# CV_Switch.net
KiCad netlist of a schematic drawn in EAGLE
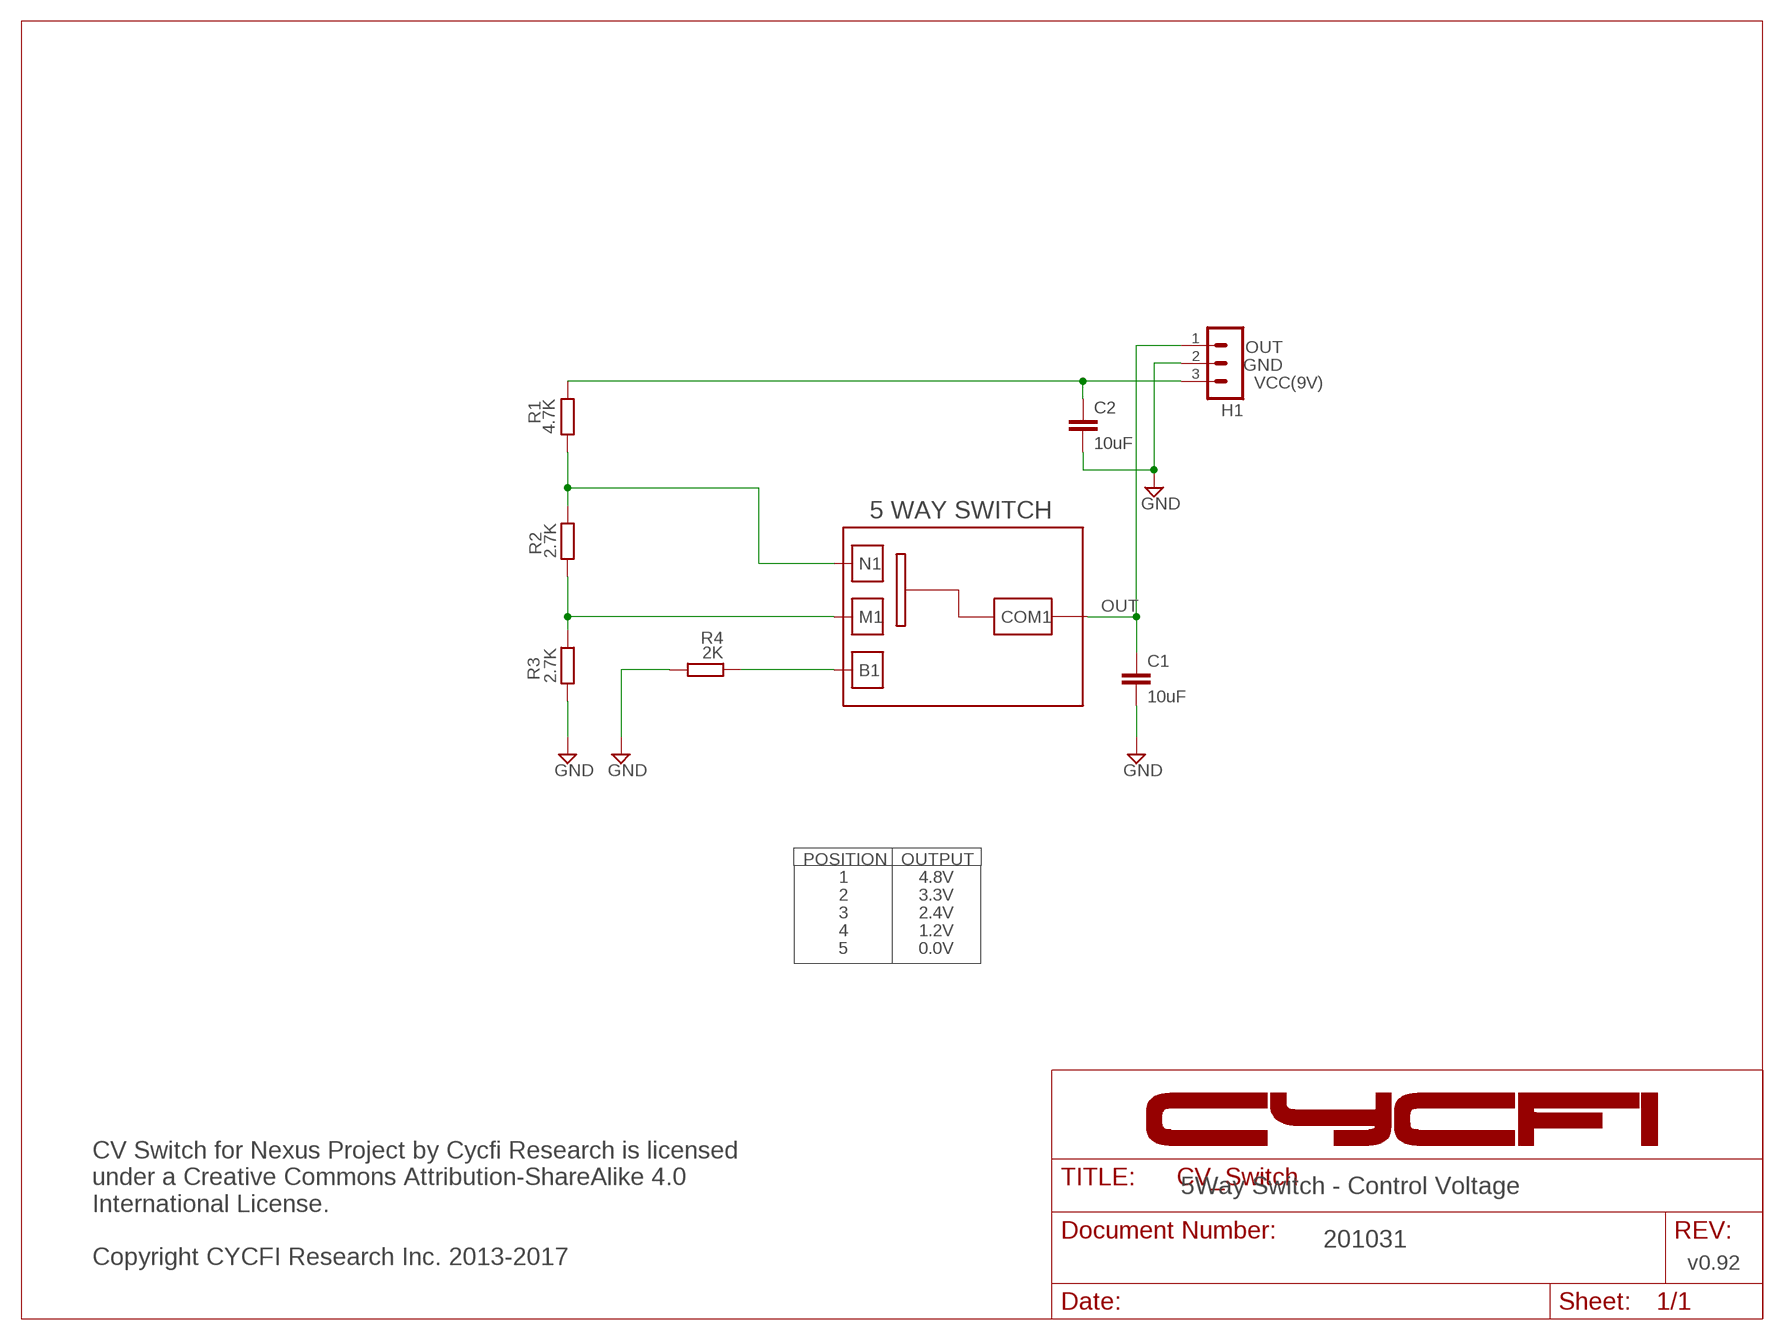
[diagram p0: schematic, sheet 1]

(export (version "E")
  (design (tool "Eeschema 10.0.6"))
  (components
    (comp (ref "C1")
      (value "10uF")
      (footprint "eagle-import:C0805")
      (libsource (lib "eagle-import") (part "C-EUC0805"))
    )
    (comp (ref "C2")
      (value "10uF")
      (footprint "eagle-import:C0805")
      (libsource (lib "eagle-import") (part "C-EUC0805"))
    )
    (comp (ref "H1")
      (value "MA03-1_EDITED")
      (footprint "eagle-import:MA03-1_")
      (libsource (lib "eagle-import") (part "MA03-1_EDITED"))
    )
    (comp (ref "R1")
      (value "4.7K")
      (footprint "eagle-import:R0402")
      (libsource (lib "eagle-import") (part "R-EU_R0402"))
    )
    (comp (ref "R2")
      (value "2.7K")
      (footprint "eagle-import:R0402")
      (libsource (lib "eagle-import") (part "R-EU_R0402"))
    )
    (comp (ref "R3")
      (value "2.7K")
      (footprint "eagle-import:R0402")
      (libsource (lib "eagle-import") (part "R-EU_R0402"))
    )
    (comp (ref "R4")
      (value "2K")
      (footprint "eagle-import:R0402")
      (libsource (lib "eagle-import") (part "R-EU_R0402"))
    )
    (comp (ref "U$1")
      (value "5WAY_SW_1")
      (footprint "eagle-import:5WAY_SW_CASTELLATED")
      (libsource (lib "eagle-import") (part "5WAY_SW_1"))
    )
  )
  (nets
    (net (code "1") (name "/OUT") (class "Default")
      (node (ref "C1") (pin "1") (pinfunction "1_1") (pintype "passive"))
      (node (ref "H1") (pin "1") (pinfunction "1_1") (pintype "passive"))
      (node (ref "U$1") (pin "COM1") (pinfunction "COM1_COM1") (pintype "bidirectional"))
    )
    (net (code "2") (name "GND") (class "Default")
      (node (ref "C1") (pin "2") (pinfunction "2_2") (pintype "passive"))
      (node (ref "C2") (pin "2") (pinfunction "2_2") (pintype "passive"))
      (node (ref "H1") (pin "2") (pinfunction "2_2") (pintype "passive"))
      (node (ref "R3") (pin "1") (pinfunction "1_1") (pintype "passive"))
      (node (ref "R4") (pin "1") (pinfunction "1_1") (pintype "passive"))
    )
    (net (code "3") (name "Net-(C2-Pad1)") (class "Default")
      (node (ref "C2") (pin "1") (pinfunction "1_1") (pintype "passive"))
      (node (ref "H1") (pin "3") (pinfunction "3_3") (pintype "passive"))
      (node (ref "R1") (pin "2") (pinfunction "2_2") (pintype "passive"))
    )
    (net (code "4") (name "Net-(R1-Pad1)") (class "Default")
      (node (ref "R1") (pin "1") (pinfunction "1_1") (pintype "passive"))
      (node (ref "R2") (pin "2") (pinfunction "2_2") (pintype "passive"))
      (node (ref "U$1") (pin "N1") (pinfunction "N1_N1") (pintype "bidirectional"))
    )
    (net (code "5") (name "Net-(R2-Pad1)") (class "Default")
      (node (ref "R2") (pin "1") (pinfunction "1_1") (pintype "passive"))
      (node (ref "R3") (pin "2") (pinfunction "2_2") (pintype "passive"))
      (node (ref "U$1") (pin "M1") (pinfunction "M1_M1") (pintype "bidirectional"))
    )
    (net (code "6") (name "Net-(R4-Pad2)") (class "Default")
      (node (ref "R4") (pin "2") (pinfunction "2_2") (pintype "passive"))
      (node (ref "U$1") (pin "B1") (pinfunction "B1_B1") (pintype "bidirectional"))
    )
  )
)
